# IO_Expansion.net
KiCad netlist of a schematic drawn in Altium Designer
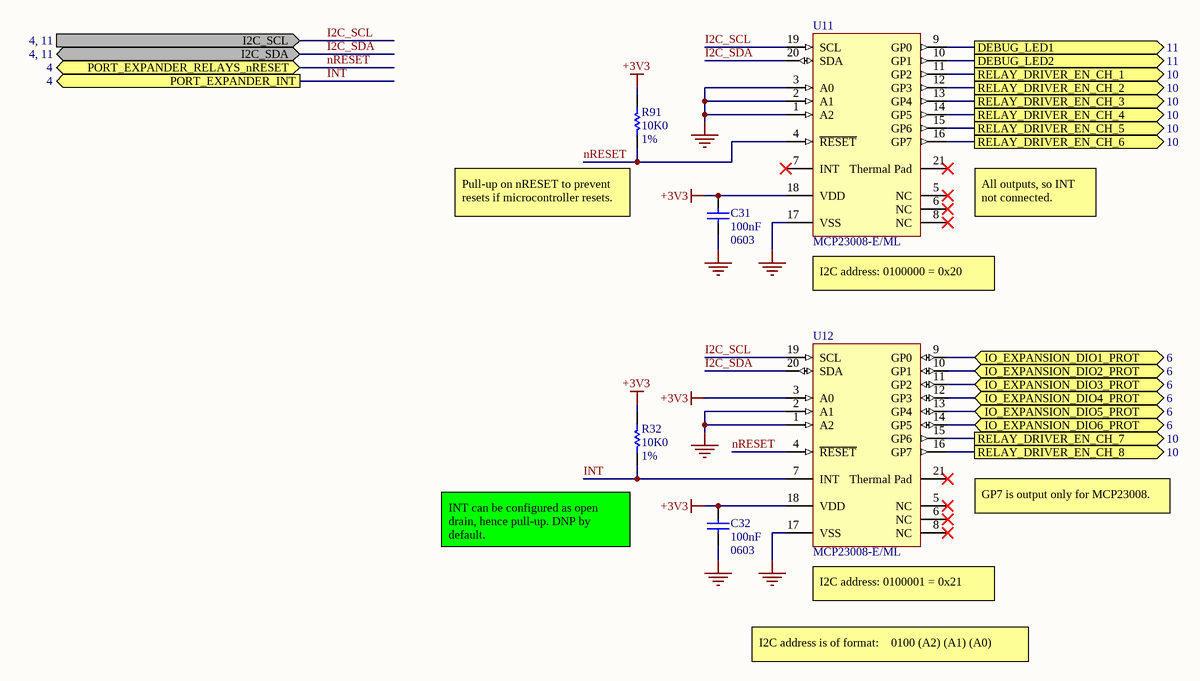
[diagram p0: IO Expansion.SchDoc]

(export (version "E")
  (design (tool "Eeschema 10.0.6"))
  (components
    (comp (ref "C31")
      (value "100nF")
      (footprint "0603 CAP SAMSUNG CL10C")
      (description "Capacitor")
      (fields (field (name "ALTIUM_VALUE") "0603") (field (name "PUBLISHER") "Altium Limited"))
      (libsource (lib "Miscellaneous Devices") (part "Cap"))
    )
    (comp (ref "C32")
      (value "100nF")
      (footprint "0603 CAP SAMSUNG CL10C")
      (description "Capacitor")
      (fields (field (name "ALTIUM_VALUE") "0603") (field (name "PUBLISHER") "Altium Limited"))
      (libsource (lib "Miscellaneous Devices") (part "Cap"))
    )
    (comp (ref "R32")
      (value "10K0")
      (footprint "0603 RES")
      (description "Resistor")
      (fields (field (name "ALTIUM_VALUE") "1%") (field (name "PUBLISHER") "Altium Limited"))
      (libsource (lib "Miscellaneous Devices") (part "Res1"))
    )
    (comp (ref "R91")
      (value "10K0")
      (footprint "0603 RES")
      (description "Resistor")
      (fields (field (name "ALTIUM_VALUE") "1%") (field (name "PUBLISHER") "Altium Limited"))
      (libsource (lib "Miscellaneous Devices") (part "Res1"))
    )
    (comp (ref "U11")
      (value "MCP23008-E/ML")
      (footprint "QFN-ML20_M")
      (description "8-Bit I/O Expander with Serial Interface, 20-Pin QFN, Extended Temperature")
      (libsource (lib "Altium Content Vault") (part "PR-BUSIC-MCP23008-21"))
    )
    (comp (ref "U12")
      (value "MCP23008-E/ML")
      (footprint "QFN-ML20_M")
      (description "8-Bit I/O Expander with Serial Interface, 20-Pin QFN, Extended Temperature")
      (libsource (lib "Altium Content Vault") (part "PR-BUSIC-MCP23008-21"))
    )
  )
  (nets
    (net (code "1") (name "+3V3") (class "Default")
      (node (ref "C31") (pin "2") (pinfunction "2_2") (pintype "passive"))
      (node (ref "C32") (pin "2") (pinfunction "2_2") (pintype "passive"))
      (node (ref "R32") (pin "1") (pinfunction "1_1") (pintype "passive"))
      (node (ref "R91") (pin "1") (pinfunction "1_1") (pintype "passive"))
      (node (ref "U11") (pin "18") (pinfunction "VDD_18") (pintype "power_in"))
      (node (ref "U12") (pin "18") (pinfunction "VDD_18") (pintype "power_in"))
      (node (ref "U12") (pin "3") (pinfunction "A0_3") (pintype "input"))
    )
    (net (code "2") (name "/DEBUG_LED1") (class "Default")
      (node (ref "U11") (pin "9") (pinfunction "GP0_9") (pintype "bidirectional"))
    )
    (net (code "3") (name "/DEBUG_LED2") (class "Default")
      (node (ref "U11") (pin "10") (pinfunction "GP1_10") (pintype "bidirectional"))
    )
    (net (code "4") (name "/I2C_SCL") (class "Default")
      (node (ref "U11") (pin "19") (pinfunction "SCL_19") (pintype "input"))
      (node (ref "U12") (pin "19") (pinfunction "SCL_19") (pintype "input"))
    )
    (net (code "5") (name "/I2C_SDA") (class "Default")
      (node (ref "U11") (pin "20") (pinfunction "SDA_20") (pintype "bidirectional"))
      (node (ref "U12") (pin "20") (pinfunction "SDA_20") (pintype "bidirectional"))
    )
    (net (code "6") (name "/INT") (class "Default")
      (node (ref "R32") (pin "2") (pinfunction "2_2") (pintype "passive"))
      (node (ref "U12") (pin "7") (pinfunction "INT_7") (pintype "open_collector"))
    )
    (net (code "7") (name "/IO_EXPANSION_DIO1_PROT") (class "Default")
      (node (ref "U12") (pin "9") (pinfunction "GP0_9") (pintype "bidirectional"))
    )
    (net (code "8") (name "/IO_EXPANSION_DIO2_PROT") (class "Default")
      (node (ref "U12") (pin "10") (pinfunction "GP1_10") (pintype "bidirectional"))
    )
    (net (code "9") (name "/IO_EXPANSION_DIO3_PROT") (class "Default")
      (node (ref "U12") (pin "11") (pinfunction "GP2_11") (pintype "bidirectional"))
    )
    (net (code "10") (name "/IO_EXPANSION_DIO4_PROT") (class "Default")
      (node (ref "U12") (pin "12") (pinfunction "GP3_12") (pintype "bidirectional"))
    )
    (net (code "11") (name "/IO_EXPANSION_DIO5_PROT") (class "Default")
      (node (ref "U12") (pin "13") (pinfunction "GP4_13") (pintype "bidirectional"))
    )
    (net (code "12") (name "/IO_EXPANSION_DIO6_PROT") (class "Default")
      (node (ref "U12") (pin "14") (pinfunction "GP5_14") (pintype "bidirectional"))
    )
    (net (code "13") (name "/RELAY_DRIVER_EN_CH_1") (class "Default")
      (node (ref "U11") (pin "11") (pinfunction "GP2_11") (pintype "bidirectional"))
    )
    (net (code "14") (name "/RELAY_DRIVER_EN_CH_2") (class "Default")
      (node (ref "U11") (pin "12") (pinfunction "GP3_12") (pintype "bidirectional"))
    )
    (net (code "15") (name "/RELAY_DRIVER_EN_CH_3") (class "Default")
      (node (ref "U11") (pin "13") (pinfunction "GP4_13") (pintype "bidirectional"))
    )
    (net (code "16") (name "/RELAY_DRIVER_EN_CH_4") (class "Default")
      (node (ref "U11") (pin "14") (pinfunction "GP5_14") (pintype "bidirectional"))
    )
    (net (code "17") (name "/RELAY_DRIVER_EN_CH_5") (class "Default")
      (node (ref "U11") (pin "15") (pinfunction "GP6_15") (pintype "output"))
    )
    (net (code "18") (name "/RELAY_DRIVER_EN_CH_6") (class "Default")
      (node (ref "U11") (pin "16") (pinfunction "GP7_16") (pintype "output"))
    )
    (net (code "19") (name "/RELAY_DRIVER_EN_CH_7") (class "Default")
      (node (ref "U12") (pin "15") (pinfunction "GP6_15") (pintype "output"))
    )
    (net (code "20") (name "/RELAY_DRIVER_EN_CH_8") (class "Default")
      (node (ref "U12") (pin "16") (pinfunction "GP7_16") (pintype "output"))
    )
    (net (code "21") (name "/nRESET") (class "Default")
      (node (ref "R91") (pin "2") (pinfunction "2_2") (pintype "passive"))
      (node (ref "U11") (pin "4") (pinfunction "~{RESET}_4") (pintype "input"))
      (node (ref "U12") (pin "4") (pinfunction "~{RESET}_4") (pintype "input"))
    )
    (net (code "22") (name "GND") (class "Default")
      (node (ref "C31") (pin "1") (pinfunction "1_1") (pintype "passive"))
      (node (ref "C32") (pin "1") (pinfunction "1_1") (pintype "passive"))
      (node (ref "U11") (pin "1") (pinfunction "A2_1") (pintype "input"))
      (node (ref "U11") (pin "17") (pinfunction "VSS_17") (pintype "power_in"))
      (node (ref "U11") (pin "2") (pinfunction "A1_2") (pintype "input"))
      (node (ref "U11") (pin "3") (pinfunction "A0_3") (pintype "input"))
      (node (ref "U12") (pin "1") (pinfunction "A2_1") (pintype "input"))
      (node (ref "U12") (pin "17") (pinfunction "VSS_17") (pintype "power_in"))
      (node (ref "U12") (pin "2") (pinfunction "A1_2") (pintype "input"))
    )
    (net (code "23") (name "unconnected-(U11-INT-Pad7)") (class "Default")
      (node (ref "U11") (pin "7") (pinfunction "INT_7") (pintype "open_collector+no_connect"))
    )
    (net (code "24") (name "unconnected-(U11-NC-Pad5)") (class "Default")
      (node (ref "U11") (pin "5") (pinfunction "NC_5") (pintype "passive+no_connect"))
    )
    (net (code "25") (name "unconnected-(U11-NC-Pad6)") (class "Default")
      (node (ref "U11") (pin "6") (pinfunction "NC_6") (pintype "passive+no_connect"))
    )
    (net (code "26") (name "unconnected-(U11-NC-Pad8)") (class "Default")
      (node (ref "U11") (pin "8") (pinfunction "NC_8") (pintype "passive+no_connect"))
    )
    (net (code "27") (name "unconnected-(U11-Thermal_Pad-Pad21)") (class "Default")
      (node (ref "U11") (pin "21") (pinfunction "Thermal_Pad_21") (pintype "passive+no_connect"))
    )
    (net (code "28") (name "unconnected-(U12-NC-Pad5)") (class "Default")
      (node (ref "U12") (pin "5") (pinfunction "NC_5") (pintype "passive+no_connect"))
    )
    (net (code "29") (name "unconnected-(U12-NC-Pad6)") (class "Default")
      (node (ref "U12") (pin "6") (pinfunction "NC_6") (pintype "passive+no_connect"))
    )
    (net (code "30") (name "unconnected-(U12-NC-Pad8)") (class "Default")
      (node (ref "U12") (pin "8") (pinfunction "NC_8") (pintype "passive+no_connect"))
    )
    (net (code "31") (name "unconnected-(U12-Thermal_Pad-Pad21)") (class "Default")
      (node (ref "U12") (pin "21") (pinfunction "Thermal_Pad_21") (pintype "passive+no_connect"))
    )
  )
)
